# DC-DC.net
KiCad netlist of a schematic drawn in Altium Designer
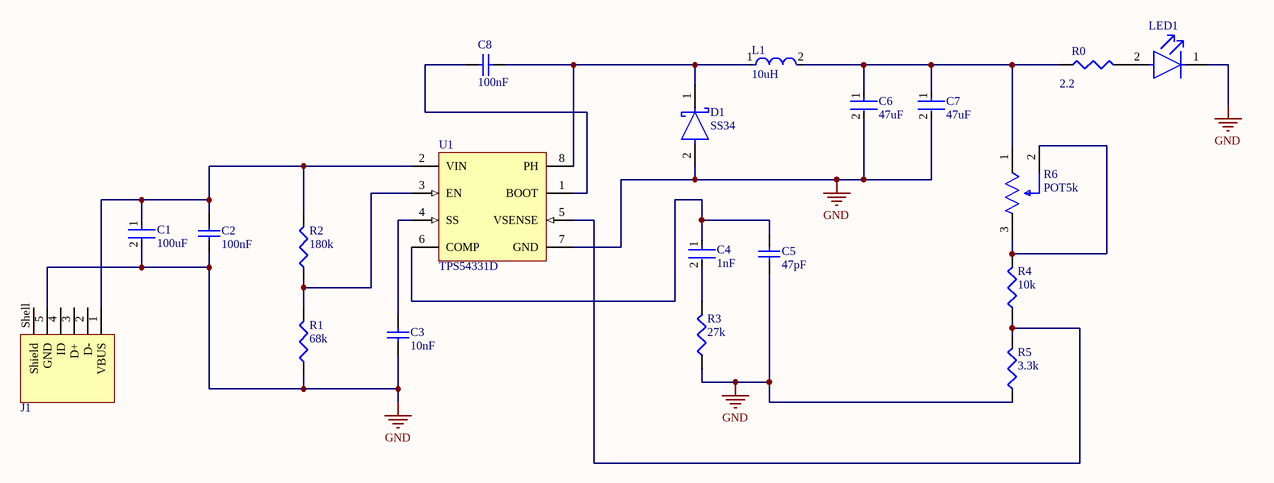
[diagram p0: DC-DC.SchDoc]

(export (version "E")
  (design (tool "Eeschema 10.0.6"))
  (components
    (comp (ref "C1")
      (value "100uF")
      (footprint "FP-C1210C-FS-MFG")
      (description "CAP CER 100UF 16V X5R 1210")
      (fields (field (name "TOLERANCE") "20%"))
      (libsource (lib "Altium Content Vault") (part "02cd4be3c70576c341d710602a673aa"))
    )
    (comp (ref "C2")
      (value "100nF")
      (footprint "CAPC1608X90X35ML10T15")
      (description "Chip Capacitor, 0.1 uF, +/- 10%, 50 V, -55 to 125 degC, 0603 (1608 Metric), RoHS, Tape and Reel")
      (fields (field (name "TOLERANCE") "10%") (field (name "VOLTAGE") "50V"))
      (libsource (lib "Altium Content Vault") (part "CAP-NP-2"))
    )
    (comp (ref "C3")
      (value "10nF")
      (footprint "CAPC1608X90X35ML10T15")
      (description "Chip Capacitor, 10 nF, +/- 10%, 50 V, -55 to 125 degC, 0603 (1608 Metric), RoHS, Tape and Reel")
      (fields (field (name "VOLTAGE") "50V") (field (name "TOLERANCE") "10%"))
      (libsource (lib "Altium Content Vault") (part "CAP-NP-2"))
    )
    (comp (ref "C4")
      (value "1nF")
      (footprint "FP-0603-L_1_6_0_15-W_0_81-IPC_A")
      (description "General Purpose Ceramic Capacitor, 0603, 1nF, 10%, X7R, 15%, 50V")
      (fields (field (name "VOLTAGE") "50V") (field (name "TOLERANCE") "10%"))
      (libsource (lib "Altium Content Vault") (part "02cd4be3c70576c341d710602a673aa"))
    )
    (comp (ref "C5")
      (value "47pF")
      (footprint "CAPC1608X90X35ML10T15")
      (fields (field (name "MANUFACTURER") "Murata") (field (name "PART NUMBER") "GRM1885C1H470JA01D"))
      (libsource (lib "Altium Content Vault") (part "CAP"))
    )
    (comp (ref "C6")
      (value "47uF")
      (footprint "FP-GRM32E-0_3-0_2-IPC_A")
      (description "Chip Multilayer Ceramic Capacitors for General Purpose, 1210, 47uF, X6S, 22%, 10%, 16V")
      (fields (field (name "VOLTAGE") "16V") (field (name "TOLERANCE") "10%"))
      (libsource (lib "Altium Content Vault") (part "02cd4be3c70576c341d710602a673aa"))
    )
    (comp (ref "C7")
      (value "47uF")
      (footprint "FP-GRM32E-0_3-0_2-IPC_A")
      (description "Chip Multilayer Ceramic Capacitors for General Purpose, 1210, 47uF, X6S, 22%, 10%, 16V")
      (fields (field (name "VOLTAGE") "16V") (field (name "TOLERANCE") "10%"))
      (libsource (lib "Altium Content Vault") (part "02cd4be3c70576c341d710602a673aa"))
    )
    (comp (ref "C8")
      (value "100nF")
      (footprint "CAPC1608X90X35ML10T15")
      (description "Chip Capacitor, 0.1 uF, +/- 10%, 50 V, -55 to 125 degC, 0603 (1608 Metric), RoHS, Tape and Reel")
      (fields (field (name "TOLERANCE") "10%") (field (name "VOLTAGE") "50V"))
      (libsource (lib "Altium Content Vault") (part "CAP-NP-2"))
    )
    (comp (ref "D1")
      (value "SS34")
      (footprint "FP-95402-MFG")
      (description "DIODE SCHOTTKY 40V 3A DO214AB")
      (fields (field (name "MANUFACTURER") "Vishay") (field (name "MANUFACTURER PART NUMBER") "SS34-E3/57T"))
      (libsource (lib "Altium Content Vault") (part "1d6ec82d83fb6aee721767c19dac4b9"))
    )
    (comp (ref "J1")
      (value "~")
      (footprint "651305142821")
      (libsource (lib "Altium Content Vault") (part "Mini USB 2.0_Type AB_Receptacle_1 Port"))
    )
    (comp (ref "L1")
      (value "10uH")
      (footprint "FP-LQH32CH_23-MFG")
      (description "Wire Wound Ferrite Inductor for Power Lines 10μH ±10% 0.572Ω 300mA 1210")
      (fields (field (name "TOLERANCE") "10%"))
      (libsource (lib "Altium Content Vault") (part "725321dda6339637d4d059423bc1c3c"))
    )
    (comp (ref "LED1")
      (value "~")
      (footprint "FP-LB_Q39G-MFG")
      (description "LED BLUE DIFFUSED 0603 SMD")
      (libsource (lib "Altium Content Vault") (part "8706943c75ba83719d021d2fdc84c58"))
    )
    (comp (ref "R0")
      (value "2.2")
      (footprint "J1-0603")
      (description "Resistor")
      (fields (field (name "PUBLISHER") "Altium Limited"))
      (libsource (lib "Miscellaneous Devices") (part "Res3"))
    )
    (comp (ref "R1")
      (value "68k")
      (footprint "J1-0603")
      (description "Resistor")
      (fields (field (name "PUBLISHER") "Altium Limited"))
      (libsource (lib "Miscellaneous Devices") (part "Res3"))
    )
    (comp (ref "R2")
      (value "180k")
      (footprint "J1-0603")
      (description "Resistor")
      (fields (field (name "PUBLISHER") "Altium Limited"))
      (libsource (lib "Miscellaneous Devices") (part "Res3"))
    )
    (comp (ref "R3")
      (value "27k")
      (footprint "J1-0603")
      (description "Resistor")
      (fields (field (name "PUBLISHER") "Altium Limited"))
      (libsource (lib "Miscellaneous Devices") (part "Res3"))
    )
    (comp (ref "R4")
      (value "10k")
      (footprint "J1-0603")
      (description "Resistor")
      (fields (field (name "PUBLISHER") "Altium Limited"))
      (libsource (lib "Miscellaneous Devices") (part "Res3"))
    )
    (comp (ref "R5")
      (value "3.3k")
      (footprint "J1-0603")
      (description "Resistor")
      (fields (field (name "PUBLISHER") "Altium Limited"))
      (libsource (lib "Miscellaneous Devices") (part "Res3"))
    )
    (comp (ref "R6")
      (value "POT5k")
      (footprint "FP-3224W-MFG")
      (description "TRIMMER 10K OHM 0.25W J LEAD TOP")
      (fields (field (name "TOLERANCE") "10%") (field (name "MANUFACTURER") "Bourns"))
      (libsource (lib "Altium Content Vault") (part "83d3d349ed884d1db45cec512f27eb6"))
    )
    (comp (ref "U1")
      (value "TPS54331D")
      (footprint "D0008A_L")
      (fields (field (name "MANUFACTURER") "Texas Instruments"))
      (libsource (lib "Altium Content Vault") (part "TI-TPS54331D8"))
    )
  )
  (nets
    (net (code "1") (name "GND") (class "Default")
      (node (ref "C1") (pin "2") (pinfunction "2_2") (pintype "passive"))
      (node (ref "C2") (pin "1") (pinfunction "1_1") (pintype "passive"))
      (node (ref "C3") (pin "1") (pinfunction "1_1") (pintype "passive"))
      (node (ref "C5") (pin "1") (pinfunction "1_1") (pintype "passive"))
      (node (ref "C6") (pin "2") (pinfunction "2_2") (pintype "passive"))
      (node (ref "C7") (pin "2") (pinfunction "2_2") (pintype "passive"))
      (node (ref "D1") (pin "2") (pinfunction "A_2") (pintype "passive"))
      (node (ref "J1") (pin "5") (pinfunction "GND_5") (pintype "passive"))
      (node (ref "LED1") (pin "1") (pinfunction "C_1") (pintype "passive"))
      (node (ref "R1") (pin "1") (pinfunction "1_1") (pintype "passive"))
      (node (ref "R3") (pin "1") (pinfunction "1_1") (pintype "passive"))
      (node (ref "R5") (pin "1") (pinfunction "1_1") (pintype "passive"))
      (node (ref "U1") (pin "7") (pinfunction "GND_7") (pintype "power_in"))
    )
    (net (code "2") (name "Net-(C4-Pad2)") (class "Default")
      (node (ref "C4") (pin "2") (pinfunction "2_2") (pintype "passive"))
      (node (ref "R3") (pin "2") (pinfunction "2_2") (pintype "passive"))
    )
    (net (code "3") (name "Net-(D1-C)") (class "Default")
      (node (ref "C8") (pin "2") (pinfunction "2_2") (pintype "passive"))
      (node (ref "D1") (pin "1") (pinfunction "C_1") (pintype "passive"))
      (node (ref "L1") (pin "1") (pinfunction "1_1") (pintype "passive"))
      (node (ref "U1") (pin "8") (pinfunction "PH_8") (pintype "power_in"))
    )
    (net (code "4") (name "Net-(J1-VBUS)") (class "Default")
      (node (ref "C1") (pin "1") (pinfunction "1_1") (pintype "passive"))
      (node (ref "C2") (pin "2") (pinfunction "2_2") (pintype "passive"))
      (node (ref "J1") (pin "1") (pinfunction "VBUS_1") (pintype "passive"))
      (node (ref "R2") (pin "2") (pinfunction "2_2") (pintype "passive"))
      (node (ref "U1") (pin "2") (pinfunction "VIN_2") (pintype "power_in"))
    )
    (net (code "5") (name "Net-(LED1-A)") (class "Default")
      (node (ref "LED1") (pin "2") (pinfunction "A_2") (pintype "passive"))
      (node (ref "R0") (pin "2") (pinfunction "2_2") (pintype "passive"))
    )
    (net (code "6") (name "Net-(R6-CCW)") (class "Default")
      (node (ref "C6") (pin "1") (pinfunction "1_1") (pintype "passive"))
      (node (ref "C7") (pin "1") (pinfunction "1_1") (pintype "passive"))
      (node (ref "L1") (pin "2") (pinfunction "2_2") (pintype "passive"))
      (node (ref "R0") (pin "1") (pinfunction "1_1") (pintype "passive"))
      (node (ref "R6") (pin "1") (pinfunction "CCW_1") (pintype "passive"))
    )
    (net (code "7") (name "Net-(R6-CW)") (class "Default")
      (node (ref "R4") (pin "2") (pinfunction "2_2") (pintype "passive"))
      (node (ref "R6") (pin "2") (pinfunction "WIPER_2") (pintype "passive"))
      (node (ref "R6") (pin "3") (pinfunction "CW_3") (pintype "passive"))
    )
    (net (code "8") (name "Net-(U1-BOOT)") (class "Default")
      (node (ref "C8") (pin "1") (pinfunction "1_1") (pintype "passive"))
      (node (ref "U1") (pin "1") (pinfunction "BOOT_1") (pintype "passive"))
    )
    (net (code "9") (name "Net-(U1-COMP)") (class "Default")
      (node (ref "C4") (pin "1") (pinfunction "1_1") (pintype "passive"))
      (node (ref "C5") (pin "2") (pinfunction "2_2") (pintype "passive"))
      (node (ref "U1") (pin "6") (pinfunction "COMP_6") (pintype "passive"))
    )
    (net (code "10") (name "Net-(U1-EN)") (class "Default")
      (node (ref "R1") (pin "2") (pinfunction "2_2") (pintype "passive"))
      (node (ref "R2") (pin "1") (pinfunction "1_1") (pintype "passive"))
      (node (ref "U1") (pin "3") (pinfunction "EN_3") (pintype "input"))
    )
    (net (code "11") (name "Net-(U1-SS)") (class "Default")
      (node (ref "C3") (pin "2") (pinfunction "2_2") (pintype "passive"))
      (node (ref "U1") (pin "4") (pinfunction "SS_4") (pintype "input"))
    )
    (net (code "12") (name "Net-(U1-VSENSE)") (class "Default")
      (node (ref "R4") (pin "1") (pinfunction "1_1") (pintype "passive"))
      (node (ref "R5") (pin "2") (pinfunction "2_2") (pintype "passive"))
      (node (ref "U1") (pin "5") (pinfunction "VSENSE_5") (pintype "input"))
    )
    (net (code "13") (name "unconnected-(J1-D+-Pad3)") (class "Default")
      (node (ref "J1") (pin "3") (pinfunction "D+_3") (pintype "passive"))
    )
    (net (code "14") (name "unconnected-(J1-D--Pad2)") (class "Default")
      (node (ref "J1") (pin "2") (pinfunction "D-_2") (pintype "passive"))
    )
    (net (code "15") (name "unconnected-(J1-ID-Pad4)") (class "Default")
      (node (ref "J1") (pin "4") (pinfunction "ID_4") (pintype "passive"))
    )
    (net (code "16") (name "unconnected-(J1-Shield-PadShell)") (class "Default")
      (node (ref "J1") (pin "Shell") (pinfunction "Shield_Shell") (pintype "passive"))
    )
  )
)
